# receiver.net
KiCad netlist of a schematic drawn in Altium Designer
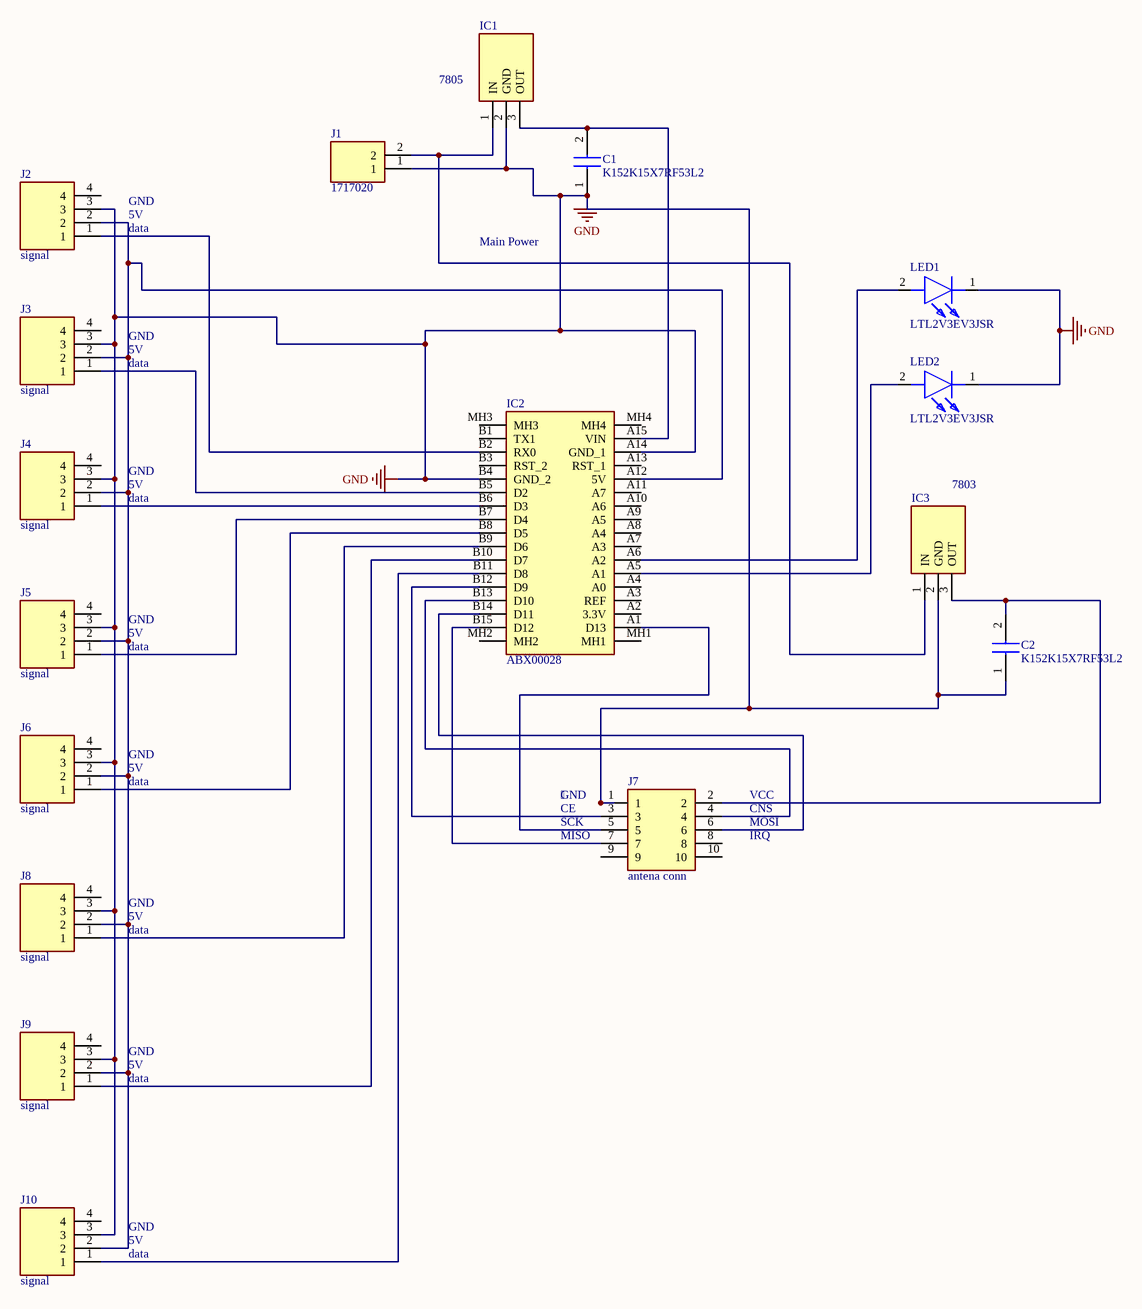
[diagram p0: receiver.SchDoc]

(export (version "E")
  (design (tool "Eeschema 10.0.6"))
  (components
    (comp (ref "C1")
      (value "K152K15X7RF53L2")
      (footprint "SamacSys:K152K15X7RF53L2")
      (description "Capacitor")
      (fields (field (name "MOUSER PART NUMBER") "594-K152K15RF53L2"))
      (libsource (lib "SamacSys") (part "K152K15X7RF53L2"))
    )
    (comp (ref "C2")
      (value "K152K15X7RF53L2")
      (footprint "SamacSys:K152K15X7RF53L2")
      (description "Capacitor")
      (fields (field (name "MOUSER PART NUMBER") "594-K152K15RF53L2"))
      (libsource (lib "SamacSys") (part "K152K15X7RF53L2"))
    )
    (comp (ref "IC1")
      (value "7805")
      (footprint "SamacSys:TO254P470X1000X1610-3P")
      (description "Integrated Circuit")
      (libsource (lib "SamacSys") (part "7805"))
    )
    (comp (ref "IC2")
      (value "ABX00028")
      (footprint "SamacSys:ABX00028")
      (description "Integrated Circuit")
      (fields (field (name "MOUSER PART NUMBER") "782-ABX00028"))
      (libsource (lib "SamacSys") (part "ABX00028"))
    )
    (comp (ref "IC3")
      (value "7803")
      (footprint "SamacSys:TO254P470X1000X1610-3P")
      (description "Integrated Circuit")
      (fields (field (name "MANUFACTURER_PART_NUMBER") "7805"))
      (libsource (lib "SamacSys") (part "7805"))
    )
    (comp (ref "J1")
      (value "1717020")
      (footprint "SamacSys:1717020")
      (description "Connector")
      (fields (field (name "MOUSER PART NUMBER") "651-1717020"))
      (libsource (lib "SamacSys") (part "1717020"))
    )
    (comp (ref "J2")
      (value "signal")
      (footprint "SamacSys:HDRV4W87P0X254_1X4_991X236X1155P")
      (description "Connector")
      (fields (field (name "MANUFACTURER_PART_NUMBER") "0022032041"))
      (libsource (lib "SamacSys") (part "0022032041"))
    )
    (comp (ref "J3")
      (value "signal")
      (footprint "SamacSys:HDRV4W87P0X254_1X4_991X236X1155P")
      (description "Connector")
      (fields (field (name "MANUFACTURER_PART_NUMBER") "0022032041"))
      (libsource (lib "SamacSys") (part "0022032041"))
    )
    (comp (ref "J4")
      (value "signal")
      (footprint "SamacSys:HDRV4W87P0X254_1X4_991X236X1155P")
      (description "Connector")
      (fields (field (name "MANUFACTURER_PART_NUMBER") "0022032041"))
      (libsource (lib "SamacSys") (part "0022032041"))
    )
    (comp (ref "J5")
      (value "signal")
      (footprint "SamacSys:HDRV4W87P0X254_1X4_991X236X1155P")
      (description "Connector")
      (fields (field (name "MANUFACTURER_PART_NUMBER") "0022032041"))
      (libsource (lib "SamacSys") (part "0022032041"))
    )
    (comp (ref "J6")
      (value "signal")
      (footprint "SamacSys:HDRV4W87P0X254_1X4_991X236X1155P")
      (description "Connector")
      (fields (field (name "MANUFACTURER_PART_NUMBER") "0022032041"))
      (libsource (lib "SamacSys") (part "0022032041"))
    )
    (comp (ref "J7")
      (value "antena conn")
      (footprint "SamacSys:HDRV10W87P254_2X5_1270X508X864P")
      (description "Connector")
      (fields (field (name "MANUFACTURER_PART_NUMBER") "0010897100"))
      (libsource (lib "SamacSys") (part "0010897100"))
    )
    (comp (ref "J8")
      (value "signal")
      (footprint "SamacSys:HDRV4W87P0X254_1X4_991X236X1155P")
      (description "Connector")
      (fields (field (name "MANUFACTURER_PART_NUMBER") "0022032041"))
      (libsource (lib "SamacSys") (part "0022032041"))
    )
    (comp (ref "J9")
      (value "signal")
      (footprint "SamacSys:HDRV4W87P0X254_1X4_991X236X1155P")
      (description "Connector")
      (fields (field (name "MANUFACTURER_PART_NUMBER") "0022032041"))
      (libsource (lib "SamacSys") (part "0022032041"))
    )
    (comp (ref "J10")
      (value "signal")
      (footprint "SamacSys:HDRV4W87P0X254_1X4_991X236X1155P")
      (description "Connector")
      (fields (field (name "MANUFACTURER_PART_NUMBER") "0022032041"))
      (libsource (lib "SamacSys") (part "0022032041"))
    )
    (comp (ref "LED1")
      (value "LTL2V3EV3JSR")
      (footprint "SamacSys:LTL2V3EV3JSR")
      (description "LED")
      (fields (field (name "MOUSER PART NUMBER") "859-LTL2V3EV3JSR"))
      (libsource (lib "SamacSys") (part "LTL2V3EV3JSR"))
    )
    (comp (ref "LED2")
      (value "LTL2V3EV3JSR")
      (footprint "SamacSys:LTL2V3EV3JSR")
      (description "LED")
      (fields (field (name "MOUSER PART NUMBER") "859-LTL2V3EV3JSR"))
      (libsource (lib "SamacSys") (part "LTL2V3EV3JSR"))
    )
  )
  (nets
    (net (code "1") (name "GND") (class "Default")
      (node (ref "C1") (pin "1") (pinfunction "1_1") (pintype "passive"))
      (node (ref "C2") (pin "1") (pinfunction "1_1") (pintype "passive"))
      (node (ref "IC1") (pin "2") (pinfunction "GND_2") (pintype "passive"))
      (node (ref "IC2") (pin "A14") (pinfunction "GND_1_A14") (pintype "passive"))
      (node (ref "IC2") (pin "B4") (pinfunction "GND_2_B4") (pintype "passive"))
      (node (ref "IC3") (pin "2") (pinfunction "GND_2") (pintype "passive"))
      (node (ref "J1") (pin "1") (pinfunction "1_1") (pintype "passive"))
      (node (ref "J10") (pin "3") (pinfunction "3_3") (pintype "passive"))
      (node (ref "J2") (pin "3") (pinfunction "3_3") (pintype "passive"))
      (node (ref "J3") (pin "3") (pinfunction "3_3") (pintype "passive"))
      (node (ref "J4") (pin "3") (pinfunction "3_3") (pintype "passive"))
      (node (ref "J5") (pin "3") (pinfunction "3_3") (pintype "passive"))
      (node (ref "J6") (pin "3") (pinfunction "3_3") (pintype "passive"))
      (node (ref "J7") (pin "1") (pinfunction "1_1") (pintype "passive"))
      (node (ref "J8") (pin "3") (pinfunction "3_3") (pintype "passive"))
      (node (ref "J9") (pin "3") (pinfunction "3_3") (pintype "passive"))
      (node (ref "LED1") (pin "1") (pinfunction "K_1") (pintype "passive"))
      (node (ref "LED2") (pin "1") (pinfunction "K_1") (pintype "passive"))
    )
    (net (code "2") (name "Net-(IC1-IN)") (class "Default")
      (node (ref "IC1") (pin "1") (pinfunction "IN_1") (pintype "passive"))
      (node (ref "IC3") (pin "1") (pinfunction "IN_1") (pintype "passive"))
      (node (ref "J1") (pin "2") (pinfunction "2_2") (pintype "passive"))
    )
    (net (code "3") (name "Net-(IC1-OUT)") (class "Default")
      (node (ref "C1") (pin "2") (pinfunction "2_2") (pintype "passive"))
      (node (ref "IC1") (pin "3") (pinfunction "OUT_3") (pintype "passive"))
      (node (ref "IC2") (pin "A15") (pinfunction "VIN_A15") (pintype "passive"))
    )
    (net (code "4") (name "Net-(IC2-5V)") (class "Default")
      (node (ref "IC2") (pin "A12") (pinfunction "5V_A12") (pintype "passive"))
      (node (ref "J10") (pin "2") (pinfunction "2_2") (pintype "passive"))
      (node (ref "J2") (pin "2") (pinfunction "2_2") (pintype "passive"))
      (node (ref "J3") (pin "2") (pinfunction "2_2") (pintype "passive"))
      (node (ref "J4") (pin "2") (pinfunction "2_2") (pintype "passive"))
      (node (ref "J5") (pin "2") (pinfunction "2_2") (pintype "passive"))
      (node (ref "J6") (pin "2") (pinfunction "2_2") (pintype "passive"))
      (node (ref "J8") (pin "2") (pinfunction "2_2") (pintype "passive"))
      (node (ref "J9") (pin "2") (pinfunction "2_2") (pintype "passive"))
    )
    (net (code "5") (name "Net-(IC2-A1)") (class "Default")
      (node (ref "IC2") (pin "A5") (pinfunction "A1_A5") (pintype "passive"))
      (node (ref "LED2") (pin "2") (pinfunction "A_2") (pintype "passive"))
    )
    (net (code "6") (name "Net-(IC2-A2)") (class "Default")
      (node (ref "IC2") (pin "A6") (pinfunction "A2_A6") (pintype "passive"))
      (node (ref "LED1") (pin "2") (pinfunction "A_2") (pintype "passive"))
    )
    (net (code "7") (name "Net-(IC2-D2)") (class "Default")
      (node (ref "IC2") (pin "B5") (pinfunction "D2_B5") (pintype "passive"))
      (node (ref "J3") (pin "1") (pinfunction "1_1") (pintype "passive"))
    )
    (net (code "8") (name "Net-(IC2-D3)") (class "Default")
      (node (ref "IC2") (pin "B6") (pinfunction "D3_B6") (pintype "passive"))
      (node (ref "J4") (pin "1") (pinfunction "1_1") (pintype "passive"))
    )
    (net (code "9") (name "Net-(IC2-D4)") (class "Default")
      (node (ref "IC2") (pin "B7") (pinfunction "D4_B7") (pintype "passive"))
      (node (ref "J5") (pin "1") (pinfunction "1_1") (pintype "passive"))
    )
    (net (code "10") (name "Net-(IC2-D5)") (class "Default")
      (node (ref "IC2") (pin "B8") (pinfunction "D5_B8") (pintype "passive"))
      (node (ref "J6") (pin "1") (pinfunction "1_1") (pintype "passive"))
    )
    (net (code "11") (name "Net-(IC2-D6)") (class "Default")
      (node (ref "IC2") (pin "B9") (pinfunction "D6_B9") (pintype "passive"))
      (node (ref "J8") (pin "1") (pinfunction "1_1") (pintype "passive"))
    )
    (net (code "12") (name "Net-(IC2-D7)") (class "Default")
      (node (ref "IC2") (pin "B10") (pinfunction "D7_B10") (pintype "passive"))
      (node (ref "J9") (pin "1") (pinfunction "1_1") (pintype "passive"))
    )
    (net (code "13") (name "Net-(IC2-D8)") (class "Default")
      (node (ref "IC2") (pin "B11") (pinfunction "D8_B11") (pintype "passive"))
      (node (ref "J10") (pin "1") (pinfunction "1_1") (pintype "passive"))
    )
    (net (code "14") (name "Net-(IC2-D9)") (class "Default")
      (node (ref "IC2") (pin "B12") (pinfunction "D9_B12") (pintype "passive"))
      (node (ref "J7") (pin "3") (pinfunction "3_3") (pintype "passive"))
    )
    (net (code "15") (name "Net-(IC2-D10)") (class "Default")
      (node (ref "IC2") (pin "B13") (pinfunction "D10_B13") (pintype "passive"))
      (node (ref "J7") (pin "4") (pinfunction "4_4") (pintype "passive"))
    )
    (net (code "16") (name "Net-(IC2-D11)") (class "Default")
      (node (ref "IC2") (pin "B14") (pinfunction "D11_B14") (pintype "passive"))
      (node (ref "J7") (pin "6") (pinfunction "6_6") (pintype "passive"))
    )
    (net (code "17") (name "Net-(IC2-D12)") (class "Default")
      (node (ref "IC2") (pin "B15") (pinfunction "D12_B15") (pintype "passive"))
      (node (ref "J7") (pin "7") (pinfunction "7_7") (pintype "passive"))
    )
    (net (code "18") (name "Net-(IC2-D13)") (class "Default")
      (node (ref "IC2") (pin "A1") (pinfunction "D13_A1") (pintype "passive"))
      (node (ref "J7") (pin "5") (pinfunction "5_5") (pintype "passive"))
    )
    (net (code "19") (name "Net-(IC2-RX0)") (class "Default")
      (node (ref "IC2") (pin "B2") (pinfunction "RX0_B2") (pintype "passive"))
      (node (ref "J2") (pin "1") (pinfunction "1_1") (pintype "passive"))
    )
    (net (code "20") (name "Net-(IC3-OUT)") (class "Default")
      (node (ref "C2") (pin "2") (pinfunction "2_2") (pintype "passive"))
      (node (ref "IC3") (pin "3") (pinfunction "OUT_3") (pintype "passive"))
      (node (ref "J7") (pin "2") (pinfunction "2_2") (pintype "passive"))
    )
    (net (code "21") (name "unconnected-(IC2-3.3V-PadA2)") (class "Default")
      (node (ref "IC2") (pin "A2") (pinfunction "3.3V_A2") (pintype "passive"))
    )
    (net (code "22") (name "unconnected-(IC2-A0-PadA4)") (class "Default")
      (node (ref "IC2") (pin "A4") (pinfunction "A0_A4") (pintype "passive"))
    )
    (net (code "23") (name "unconnected-(IC2-A3-PadA7)") (class "Default")
      (node (ref "IC2") (pin "A7") (pinfunction "A3_A7") (pintype "passive"))
    )
    (net (code "24") (name "unconnected-(IC2-A4-PadA8)") (class "Default")
      (node (ref "IC2") (pin "A8") (pinfunction "A4_A8") (pintype "passive"))
    )
    (net (code "25") (name "unconnected-(IC2-A5-PadA9)") (class "Default")
      (node (ref "IC2") (pin "A9") (pinfunction "A5_A9") (pintype "passive"))
    )
    (net (code "26") (name "unconnected-(IC2-A6-PadA10)") (class "Default")
      (node (ref "IC2") (pin "A10") (pinfunction "A6_A10") (pintype "passive"))
    )
    (net (code "27") (name "unconnected-(IC2-A7-PadA11)") (class "Default")
      (node (ref "IC2") (pin "A11") (pinfunction "A7_A11") (pintype "passive"))
    )
    (net (code "28") (name "unconnected-(IC2-PadMH1)") (class "Default")
      (node (ref "IC2") (pin "MH1") (pinfunction "MH1_MH1") (pintype "passive"))
    )
    (net (code "29") (name "unconnected-(IC2-PadMH2)") (class "Default")
      (node (ref "IC2") (pin "MH2") (pinfunction "MH2_MH2") (pintype "passive"))
    )
    (net (code "30") (name "unconnected-(IC2-PadMH3)") (class "Default")
      (node (ref "IC2") (pin "MH3") (pinfunction "MH3_MH3") (pintype "passive"))
    )
    (net (code "31") (name "unconnected-(IC2-PadMH4)") (class "Default")
      (node (ref "IC2") (pin "MH4") (pinfunction "MH4_MH4") (pintype "passive"))
    )
    (net (code "32") (name "unconnected-(IC2-REF-PadA3)") (class "Default")
      (node (ref "IC2") (pin "A3") (pinfunction "REF_A3") (pintype "passive"))
    )
    (net (code "33") (name "unconnected-(IC2-RST_1-PadA13)") (class "Default")
      (node (ref "IC2") (pin "A13") (pinfunction "RST_1_A13") (pintype "passive"))
    )
    (net (code "34") (name "unconnected-(IC2-RST_2-PadB3)") (class "Default")
      (node (ref "IC2") (pin "B3") (pinfunction "RST_2_B3") (pintype "passive"))
    )
    (net (code "35") (name "unconnected-(IC2-TX1-PadB1)") (class "Default")
      (node (ref "IC2") (pin "B1") (pinfunction "TX1_B1") (pintype "passive"))
    )
    (net (code "36") (name "unconnected-(J2-Pad4)") (class "Default")
      (node (ref "J2") (pin "4") (pinfunction "4_4") (pintype "passive"))
    )
    (net (code "37") (name "unconnected-(J3-Pad4)") (class "Default")
      (node (ref "J3") (pin "4") (pinfunction "4_4") (pintype "passive"))
    )
    (net (code "38") (name "unconnected-(J4-Pad4)") (class "Default")
      (node (ref "J4") (pin "4") (pinfunction "4_4") (pintype "passive"))
    )
    (net (code "39") (name "unconnected-(J5-Pad4)") (class "Default")
      (node (ref "J5") (pin "4") (pinfunction "4_4") (pintype "passive"))
    )
    (net (code "40") (name "unconnected-(J6-Pad4)") (class "Default")
      (node (ref "J6") (pin "4") (pinfunction "4_4") (pintype "passive"))
    )
    (net (code "41") (name "unconnected-(J7-Pad8)") (class "Default")
      (node (ref "J7") (pin "8") (pinfunction "8_8") (pintype "passive"))
    )
    (net (code "42") (name "unconnected-(J7-Pad9)") (class "Default")
      (node (ref "J7") (pin "9") (pinfunction "9_9") (pintype "passive"))
    )
    (net (code "43") (name "unconnected-(J7-Pad10)") (class "Default")
      (node (ref "J7") (pin "10") (pinfunction "10_10") (pintype "passive"))
    )
    (net (code "44") (name "unconnected-(J8-Pad4)") (class "Default")
      (node (ref "J8") (pin "4") (pinfunction "4_4") (pintype "passive"))
    )
    (net (code "45") (name "unconnected-(J9-Pad4)") (class "Default")
      (node (ref "J9") (pin "4") (pinfunction "4_4") (pintype "passive"))
    )
    (net (code "46") (name "unconnected-(J10-Pad4)") (class "Default")
      (node (ref "J10") (pin "4") (pinfunction "4_4") (pintype "passive"))
    )
  )
)
